# untitled.net
KiCad netlist of a schematic drawn in EAGLE
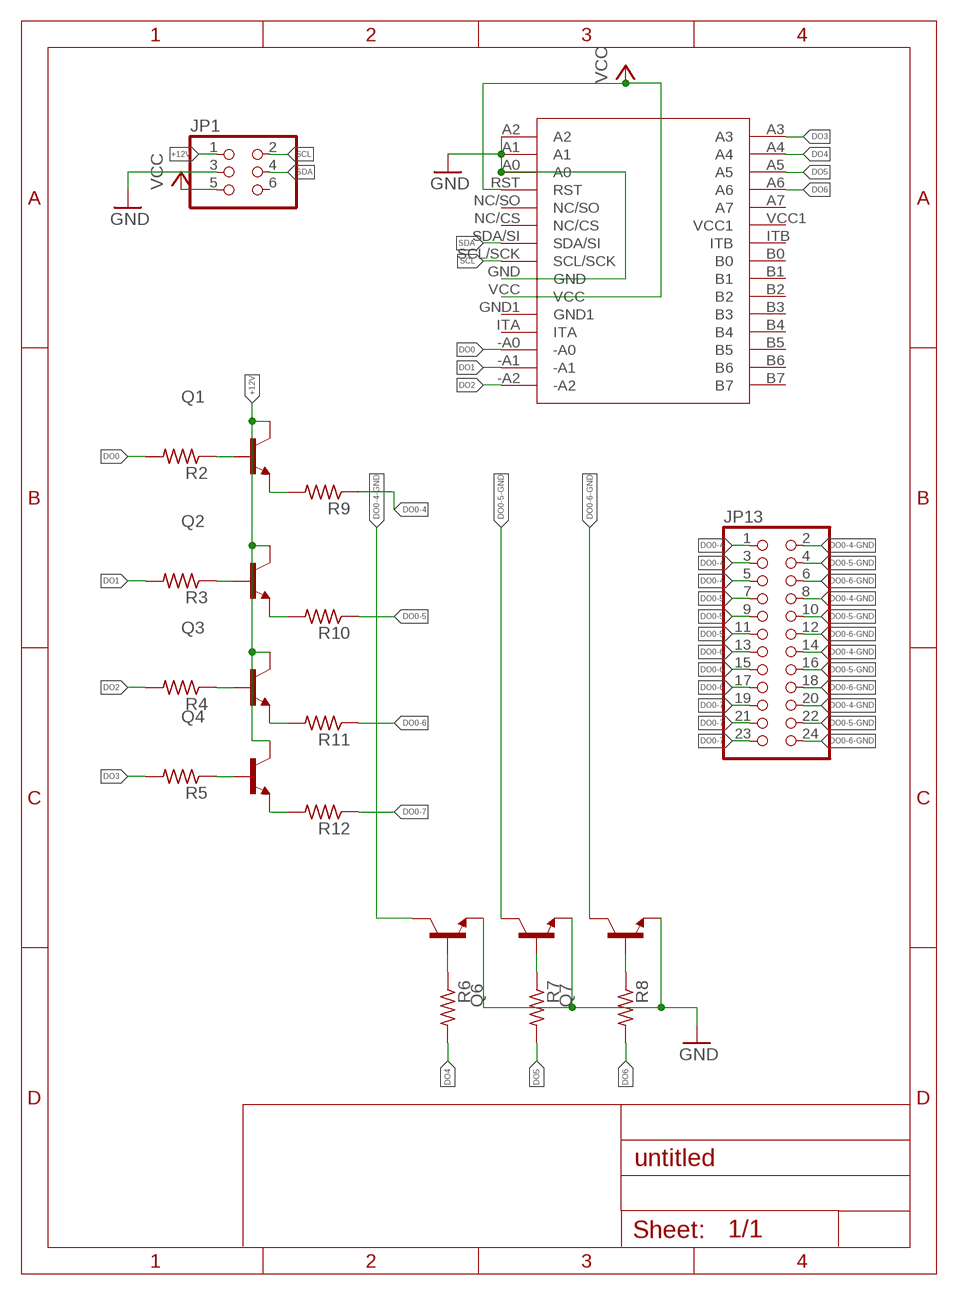
[diagram p0: schematic, sheet 1]

(export (version "E")
  (design (tool "Eeschema 10.0.6"))
  (components
    (comp (ref "JP1")
      (value "PINHD-2X3")
      (footprint "eagle-import:2X03")
      (libsource (lib "eagle-import") (part "PINHD-2X3"))
    )
    (comp (ref "JP13")
      (value "PINHD-2X12")
      (footprint "eagle-import:2X12")
      (libsource (lib "eagle-import") (part "PINHD-2X12"))
    )
    (comp (ref "MCP1")
      (value "MCP23017")
      (footprint "eagle-import:MCP23017")
      (libsource (lib "eagle-import") (part "MCP23017"))
    )
    (comp (ref "Q1")
      (value "BCW31SMD")
      (footprint "eagle-import:SOT23-BEC")
      (fields (field (name "MF") "ON Semiconductor") (field (name "MP") "BCW31"))
      (libsource (lib "eagle-import") (part "BCW31SMD"))
    )
    (comp (ref "Q2")
      (value "BCW31SMD")
      (footprint "eagle-import:SOT23-BEC")
      (fields (field (name "MF") "ON Semiconductor") (field (name "MP") "BCW31"))
      (libsource (lib "eagle-import") (part "BCW31SMD"))
    )
    (comp (ref "Q3")
      (value "BCW31SMD")
      (footprint "eagle-import:SOT23-BEC")
      (fields (field (name "MF") "ON Semiconductor") (field (name "MP") "BCW31"))
      (libsource (lib "eagle-import") (part "BCW31SMD"))
    )
    (comp (ref "Q4")
      (value "BCW31SMD")
      (footprint "eagle-import:SOT23-BEC")
      (fields (field (name "MF") "ON Semiconductor") (field (name "MP") "BCW31"))
      (libsource (lib "eagle-import") (part "BCW31SMD"))
    )
    (comp (ref "Q5")
      (value "BCW31SMD")
      (footprint "eagle-import:SOT23-BEC")
      (fields (field (name "MF") "ON Semiconductor") (field (name "MP") "BCW31"))
      (libsource (lib "eagle-import") (part "BCW31SMD"))
    )
    (comp (ref "Q6")
      (value "BCW31SMD")
      (footprint "eagle-import:SOT23-BEC")
      (fields (field (name "MF") "ON Semiconductor") (field (name "MP") "BCW31"))
      (libsource (lib "eagle-import") (part "BCW31SMD"))
    )
    (comp (ref "Q7")
      (value "BCW31SMD")
      (footprint "eagle-import:SOT23-BEC")
      (fields (field (name "MF") "ON Semiconductor") (field (name "MP") "BCW31"))
      (libsource (lib "eagle-import") (part "BCW31SMD"))
    )
    (comp (ref "R2")
      (value "R-US_M0805")
      (footprint "eagle-import:M0805")
      (libsource (lib "eagle-import") (part "R-US_M0805"))
    )
    (comp (ref "R3")
      (value "R-US_M0805")
      (footprint "eagle-import:M0805")
      (libsource (lib "eagle-import") (part "R-US_M0805"))
    )
    (comp (ref "R4")
      (value "R-US_M0805")
      (footprint "eagle-import:M0805")
      (libsource (lib "eagle-import") (part "R-US_M0805"))
    )
    (comp (ref "R5")
      (value "R-US_M0805")
      (footprint "eagle-import:M0805")
      (libsource (lib "eagle-import") (part "R-US_M0805"))
    )
    (comp (ref "R6")
      (value "R-US_M0805")
      (footprint "eagle-import:M0805")
      (libsource (lib "eagle-import") (part "R-US_M0805"))
    )
    (comp (ref "R7")
      (value "R-US_M0805")
      (footprint "eagle-import:M0805")
      (libsource (lib "eagle-import") (part "R-US_M0805"))
    )
    (comp (ref "R8")
      (value "R-US_M0805")
      (footprint "eagle-import:M0805")
      (libsource (lib "eagle-import") (part "R-US_M0805"))
    )
    (comp (ref "R9")
      (value "R-US_M0805")
      (footprint "eagle-import:M0805")
      (libsource (lib "eagle-import") (part "R-US_M0805"))
    )
    (comp (ref "R10")
      (value "R-US_M0805")
      (footprint "eagle-import:M0805")
      (libsource (lib "eagle-import") (part "R-US_M0805"))
    )
    (comp (ref "R11")
      (value "R-US_M0805")
      (footprint "eagle-import:M0805")
      (libsource (lib "eagle-import") (part "R-US_M0805"))
    )
    (comp (ref "R12")
      (value "R-US_M0805")
      (footprint "eagle-import:M0805")
      (libsource (lib "eagle-import") (part "R-US_M0805"))
    )
  )
  (nets
    (net (code "1") (name "+12V") (class "Default")
      (node (ref "JP1") (pin "1") (pinfunction "1_1") (pintype "passive"))
      (node (ref "Q1") (pin "C") (pinfunction "C_C") (pintype "passive"))
      (node (ref "Q2") (pin "C") (pinfunction "C_C") (pintype "passive"))
      (node (ref "Q3") (pin "C") (pinfunction "C_C") (pintype "passive"))
      (node (ref "Q4") (pin "C") (pinfunction "C_C") (pintype "passive"))
    )
    (net (code "2") (name "DO0") (class "Default")
      (node (ref "MCP1") (pin "-A0") (pinfunction "-A0_-A0") (pintype "bidirectional"))
      (node (ref "R2") (pin "2") (pinfunction "2_2") (pintype "passive"))
    )
    (net (code "3") (name "DO0-4") (class "Default")
      (node (ref "JP13") (pin "1") (pinfunction "1_1") (pintype "passive"))
      (node (ref "JP13") (pin "3") (pinfunction "3_3") (pintype "passive"))
      (node (ref "JP13") (pin "5") (pinfunction "5_5") (pintype "passive"))
      (node (ref "R9") (pin "1") (pinfunction "1_1") (pintype "passive"))
    )
    (net (code "4") (name "DO0-4-GND") (class "Default")
      (node (ref "JP13") (pin "14") (pinfunction "14_14") (pintype "passive"))
      (node (ref "JP13") (pin "2") (pinfunction "2_2") (pintype "passive"))
      (node (ref "JP13") (pin "20") (pinfunction "20_20") (pintype "passive"))
      (node (ref "JP13") (pin "8") (pinfunction "8_8") (pintype "passive"))
      (node (ref "Q5") (pin "C") (pinfunction "C_C") (pintype "passive"))
    )
    (net (code "5") (name "DO0-5") (class "Default")
      (node (ref "JP13") (pin "11") (pinfunction "11_11") (pintype "passive"))
      (node (ref "JP13") (pin "7") (pinfunction "7_7") (pintype "passive"))
      (node (ref "JP13") (pin "9") (pinfunction "9_9") (pintype "passive"))
      (node (ref "R10") (pin "1") (pinfunction "1_1") (pintype "passive"))
    )
    (net (code "6") (name "DO0-5-GND") (class "Default")
      (node (ref "JP13") (pin "10") (pinfunction "10_10") (pintype "passive"))
      (node (ref "JP13") (pin "16") (pinfunction "16_16") (pintype "passive"))
      (node (ref "JP13") (pin "22") (pinfunction "22_22") (pintype "passive"))
      (node (ref "JP13") (pin "4") (pinfunction "4_4") (pintype "passive"))
      (node (ref "Q6") (pin "C") (pinfunction "C_C") (pintype "passive"))
    )
    (net (code "7") (name "DO0-6") (class "Default")
      (node (ref "JP13") (pin "13") (pinfunction "13_13") (pintype "passive"))
      (node (ref "JP13") (pin "15") (pinfunction "15_15") (pintype "passive"))
      (node (ref "JP13") (pin "17") (pinfunction "17_17") (pintype "passive"))
      (node (ref "R11") (pin "1") (pinfunction "1_1") (pintype "passive"))
    )
    (net (code "8") (name "DO0-6-GND") (class "Default")
      (node (ref "JP13") (pin "12") (pinfunction "12_12") (pintype "passive"))
      (node (ref "JP13") (pin "18") (pinfunction "18_18") (pintype "passive"))
      (node (ref "JP13") (pin "24") (pinfunction "24_24") (pintype "passive"))
      (node (ref "JP13") (pin "6") (pinfunction "6_6") (pintype "passive"))
      (node (ref "Q7") (pin "C") (pinfunction "C_C") (pintype "passive"))
    )
    (net (code "9") (name "DO0-7") (class "Default")
      (node (ref "JP13") (pin "19") (pinfunction "19_19") (pintype "passive"))
      (node (ref "JP13") (pin "21") (pinfunction "21_21") (pintype "passive"))
      (node (ref "JP13") (pin "23") (pinfunction "23_23") (pintype "passive"))
      (node (ref "R12") (pin "1") (pinfunction "1_1") (pintype "passive"))
    )
    (net (code "10") (name "DO1") (class "Default")
      (node (ref "MCP1") (pin "-A1") (pinfunction "-A1_-A1") (pintype "bidirectional"))
      (node (ref "R3") (pin "2") (pinfunction "2_2") (pintype "passive"))
    )
    (net (code "11") (name "DO2") (class "Default")
      (node (ref "MCP1") (pin "-A2") (pinfunction "-A2_-A2") (pintype "bidirectional"))
      (node (ref "R4") (pin "2") (pinfunction "2_2") (pintype "passive"))
    )
    (net (code "12") (name "DO3") (class "Default")
      (node (ref "MCP1") (pin "A3") (pinfunction "A3_A3") (pintype "bidirectional"))
      (node (ref "R5") (pin "2") (pinfunction "2_2") (pintype "passive"))
    )
    (net (code "13") (name "DO4") (class "Default")
      (node (ref "MCP1") (pin "A4") (pinfunction "A4_A4") (pintype "bidirectional"))
      (node (ref "R6") (pin "2") (pinfunction "2_2") (pintype "passive"))
    )
    (net (code "14") (name "DO5") (class "Default")
      (node (ref "MCP1") (pin "A5") (pinfunction "A5_A5") (pintype "bidirectional"))
      (node (ref "R7") (pin "2") (pinfunction "2_2") (pintype "passive"))
    )
    (net (code "15") (name "DO6") (class "Default")
      (node (ref "MCP1") (pin "A6") (pinfunction "A6_A6") (pintype "bidirectional"))
      (node (ref "R8") (pin "2") (pinfunction "2_2") (pintype "passive"))
    )
    (net (code "16") (name "GND") (class "Default")
      (node (ref "JP1") (pin "3") (pinfunction "3_3") (pintype "passive"))
      (node (ref "MCP1") (pin "A0") (pinfunction "A0_A0") (pintype "bidirectional"))
      (node (ref "MCP1") (pin "A1") (pinfunction "A1_A1") (pintype "bidirectional"))
      (node (ref "MCP1") (pin "A2") (pinfunction "A2_A2") (pintype "bidirectional"))
      (node (ref "MCP1") (pin "GND") (pinfunction "GND_GND") (pintype "bidirectional"))
      (node (ref "Q5") (pin "E") (pinfunction "E_E") (pintype "passive"))
      (node (ref "Q6") (pin "E") (pinfunction "E_E") (pintype "passive"))
      (node (ref "Q7") (pin "E") (pinfunction "E_E") (pintype "passive"))
    )
    (net (code "17") (name "Net-(Q1-PadB)") (class "Default")
      (node (ref "Q1") (pin "B") (pinfunction "B_B") (pintype "passive"))
      (node (ref "R2") (pin "1") (pinfunction "1_1") (pintype "passive"))
    )
    (net (code "18") (name "Net-(Q1-PadE)") (class "Default")
      (node (ref "Q1") (pin "E") (pinfunction "E_E") (pintype "passive"))
      (node (ref "R9") (pin "2") (pinfunction "2_2") (pintype "passive"))
    )
    (net (code "19") (name "Net-(Q2-PadB)") (class "Default")
      (node (ref "Q2") (pin "B") (pinfunction "B_B") (pintype "passive"))
      (node (ref "R3") (pin "1") (pinfunction "1_1") (pintype "passive"))
    )
    (net (code "20") (name "Net-(Q2-PadE)") (class "Default")
      (node (ref "Q2") (pin "E") (pinfunction "E_E") (pintype "passive"))
      (node (ref "R10") (pin "2") (pinfunction "2_2") (pintype "passive"))
    )
    (net (code "21") (name "Net-(Q3-PadB)") (class "Default")
      (node (ref "Q3") (pin "B") (pinfunction "B_B") (pintype "passive"))
      (node (ref "R4") (pin "1") (pinfunction "1_1") (pintype "passive"))
    )
    (net (code "22") (name "Net-(Q3-PadE)") (class "Default")
      (node (ref "Q3") (pin "E") (pinfunction "E_E") (pintype "passive"))
      (node (ref "R11") (pin "2") (pinfunction "2_2") (pintype "passive"))
    )
    (net (code "23") (name "Net-(Q4-PadB)") (class "Default")
      (node (ref "Q4") (pin "B") (pinfunction "B_B") (pintype "passive"))
      (node (ref "R5") (pin "1") (pinfunction "1_1") (pintype "passive"))
    )
    (net (code "24") (name "Net-(Q4-PadE)") (class "Default")
      (node (ref "Q4") (pin "E") (pinfunction "E_E") (pintype "passive"))
      (node (ref "R12") (pin "2") (pinfunction "2_2") (pintype "passive"))
    )
    (net (code "25") (name "Net-(Q5-PadB)") (class "Default")
      (node (ref "Q5") (pin "B") (pinfunction "B_B") (pintype "passive"))
      (node (ref "R6") (pin "1") (pinfunction "1_1") (pintype "passive"))
    )
    (net (code "26") (name "Net-(Q6-PadB)") (class "Default")
      (node (ref "Q6") (pin "B") (pinfunction "B_B") (pintype "passive"))
      (node (ref "R7") (pin "1") (pinfunction "1_1") (pintype "passive"))
    )
    (net (code "27") (name "Net-(Q7-PadB)") (class "Default")
      (node (ref "Q7") (pin "B") (pinfunction "B_B") (pintype "passive"))
      (node (ref "R8") (pin "1") (pinfunction "1_1") (pintype "passive"))
    )
    (net (code "28") (name "SCL") (class "Default")
      (node (ref "JP1") (pin "2") (pinfunction "2_2") (pintype "passive"))
      (node (ref "MCP1") (pin "SCL/SCK") (pinfunction "SCL/SCK_SCL/SCK") (pintype "bidirectional"))
    )
    (net (code "29") (name "SDA") (class "Default")
      (node (ref "JP1") (pin "4") (pinfunction "4_4") (pintype "passive"))
      (node (ref "MCP1") (pin "SDA/SI") (pinfunction "SDA/SI_SDA/SI") (pintype "bidirectional"))
    )
    (net (code "30") (name "VCC") (class "Default")
      (node (ref "JP1") (pin "5") (pinfunction "5_5") (pintype "passive"))
      (node (ref "MCP1") (pin "RST") (pinfunction "RST_RST") (pintype "bidirectional"))
      (node (ref "MCP1") (pin "VCC") (pinfunction "VCC_VCC") (pintype "bidirectional"))
    )
    (net (code "31") (name "unconnected-(JP1-Pad6)") (class "Default")
      (node (ref "JP1") (pin "6") (pinfunction "6_6") (pintype "passive"))
    )
    (net (code "32") (name "unconnected-(MCP1-PadA7)") (class "Default")
      (node (ref "MCP1") (pin "A7") (pinfunction "A7_A7") (pintype "bidirectional"))
    )
    (net (code "33") (name "unconnected-(MCP1-PadB0)") (class "Default")
      (node (ref "MCP1") (pin "B0") (pinfunction "B0_B0") (pintype "bidirectional"))
    )
    (net (code "34") (name "unconnected-(MCP1-PadB1)") (class "Default")
      (node (ref "MCP1") (pin "B1") (pinfunction "B1_B1") (pintype "bidirectional"))
    )
    (net (code "35") (name "unconnected-(MCP1-PadB2)") (class "Default")
      (node (ref "MCP1") (pin "B2") (pinfunction "B2_B2") (pintype "bidirectional"))
    )
    (net (code "36") (name "unconnected-(MCP1-PadB3)") (class "Default")
      (node (ref "MCP1") (pin "B3") (pinfunction "B3_B3") (pintype "bidirectional"))
    )
    (net (code "37") (name "unconnected-(MCP1-PadB4)") (class "Default")
      (node (ref "MCP1") (pin "B4") (pinfunction "B4_B4") (pintype "bidirectional"))
    )
    (net (code "38") (name "unconnected-(MCP1-PadB5)") (class "Default")
      (node (ref "MCP1") (pin "B5") (pinfunction "B5_B5") (pintype "bidirectional"))
    )
    (net (code "39") (name "unconnected-(MCP1-PadB6)") (class "Default")
      (node (ref "MCP1") (pin "B6") (pinfunction "B6_B6") (pintype "bidirectional"))
    )
    (net (code "40") (name "unconnected-(MCP1-PadB7)") (class "Default")
      (node (ref "MCP1") (pin "B7") (pinfunction "B7_B7") (pintype "bidirectional"))
    )
    (net (code "41") (name "unconnected-(MCP1-PadGND1)") (class "Default")
      (node (ref "MCP1") (pin "GND1") (pinfunction "GND1_GND1") (pintype "bidirectional"))
    )
    (net (code "42") (name "unconnected-(MCP1-PadITA)") (class "Default")
      (node (ref "MCP1") (pin "ITA") (pinfunction "ITA_ITA") (pintype "bidirectional"))
    )
    (net (code "43") (name "unconnected-(MCP1-PadITB)") (class "Default")
      (node (ref "MCP1") (pin "ITB") (pinfunction "ITB_ITB") (pintype "bidirectional"))
    )
    (net (code "44") (name "unconnected-(MCP1-PadNC{slash}CS)") (class "Default")
      (node (ref "MCP1") (pin "NC/CS") (pinfunction "NC/CS_NC/CS") (pintype "bidirectional"))
    )
    (net (code "45") (name "unconnected-(MCP1-PadNC{slash}SO)") (class "Default")
      (node (ref "MCP1") (pin "NC/SO") (pinfunction "NC/SO_NC/SO") (pintype "bidirectional"))
    )
    (net (code "46") (name "unconnected-(MCP1-PadVCC1)") (class "Default")
      (node (ref "MCP1") (pin "VCC1") (pinfunction "VCC1_VCC1") (pintype "bidirectional"))
    )
  )
)
